# RobotFish.net
KiCad netlist of a schematic drawn in EAGLE
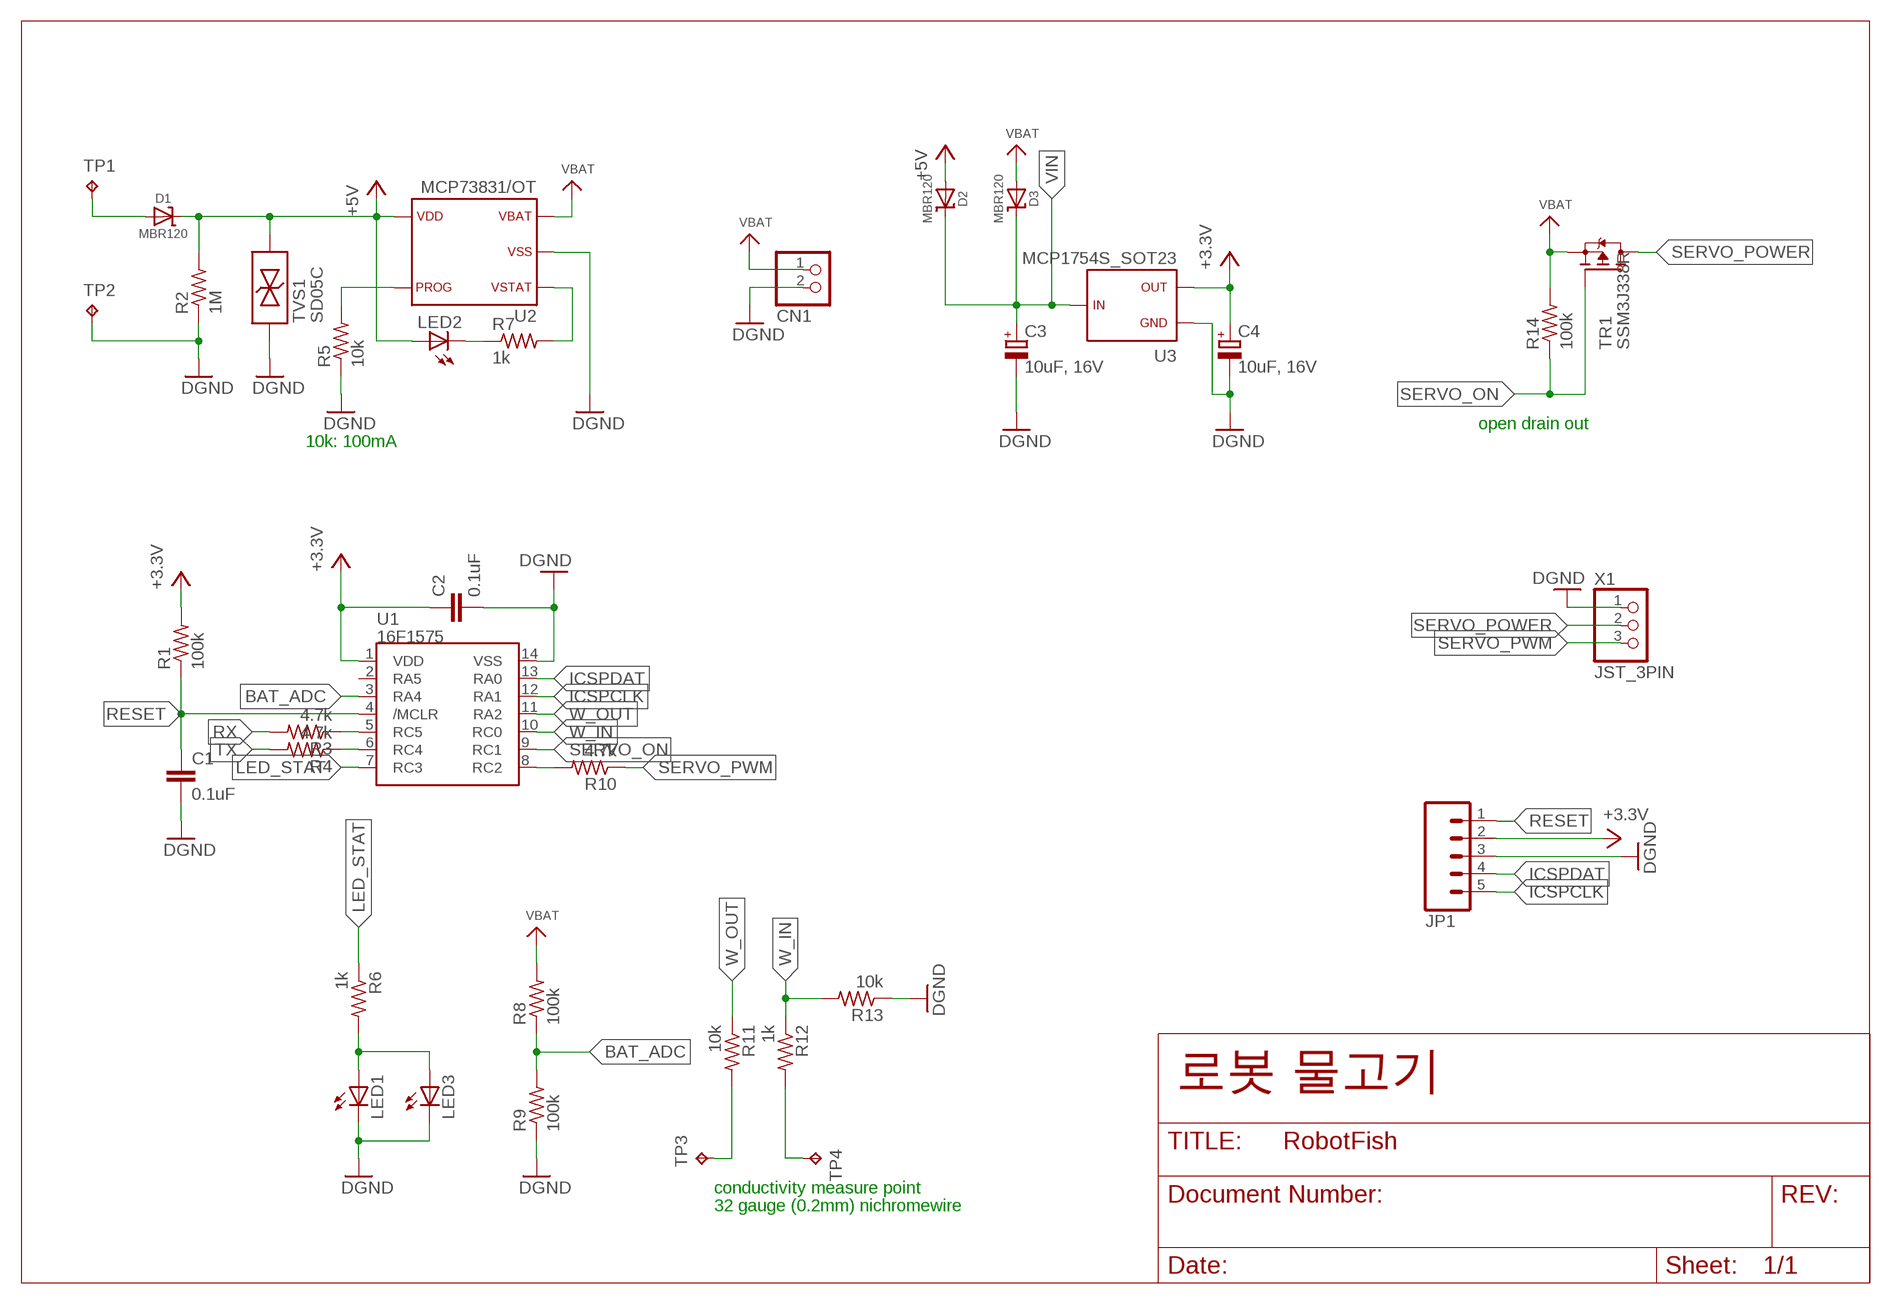
[diagram p0: schematic, sheet 1]

(export (version "E")
  (design (tool "Eeschema 10.0.6"))
  (components
    (comp (ref "C1")
      (value "0.1uF")
      (footprint "eagle-import:C0603(1608)")
      (libsource (lib "eagle-import") (part "C0603(1608)"))
    )
    (comp (ref "C2")
      (value "0.1uF")
      (footprint "eagle-import:C0603(1608)")
      (libsource (lib "eagle-import") (part "C0603(1608)"))
    )
    (comp (ref "C3")
      (value "10uF, 16V")
      (footprint "eagle-import:C1206(3216)-A")
      (libsource (lib "eagle-import") (part "C-TANTAL-A"))
    )
    (comp (ref "C4")
      (value "10uF, 16V")
      (footprint "eagle-import:C1206(3216)-A")
      (libsource (lib "eagle-import") (part "C-TANTAL-A"))
    )
    (comp (ref "CN1")
      (value "JST_2PIN-THM-RA")
      (footprint "eagle-import:JST-PH-2-THM-RA")
      (libsource (lib "eagle-import") (part "JST_2PIN-THM-RA"))
    )
    (comp (ref "D1")
      (value "MBR120")
      (footprint "eagle-import:SOD-123")
      (libsource (lib "eagle-import") (part "DIODE-SCHOTTKYSOD-123"))
    )
    (comp (ref "D2")
      (value "MBR120")
      (footprint "eagle-import:SOD-123")
      (libsource (lib "eagle-import") (part "DIODE-SCHOTTKYSOD-123"))
    )
    (comp (ref "D3")
      (value "MBR120")
      (footprint "eagle-import:SOD-123")
      (libsource (lib "eagle-import") (part "DIODE-SCHOTTKYSOD-123"))
    )
    (comp (ref "JP1")
      (value "M05PTH")
      (footprint "eagle-import:1X05")
      (libsource (lib "eagle-import") (part "M05PTH"))
    )
    (comp (ref "LED1")
      (value "LED0603")
      (footprint "eagle-import:LED-0603")
      (libsource (lib "eagle-import") (part "LED0603"))
    )
    (comp (ref "LED2")
      (value "LED0603")
      (footprint "eagle-import:LED-0603")
      (libsource (lib "eagle-import") (part "LED0603"))
    )
    (comp (ref "LED3")
      (value "LED3MM")
      (footprint "eagle-import:LED3MM")
      (libsource (lib "eagle-import") (part "LED3MM"))
    )
    (comp (ref "R1")
      (value "100k")
      (footprint "eagle-import:R0603(1608)")
      (libsource (lib "eagle-import") (part "R0603(1608)"))
    )
    (comp (ref "R2")
      (value "1M")
      (footprint "eagle-import:R0603(1608)")
      (libsource (lib "eagle-import") (part "R0603(1608)"))
    )
    (comp (ref "R3")
      (value "4.7k")
      (footprint "eagle-import:R0603(1608)")
      (libsource (lib "eagle-import") (part "R0603(1608)"))
    )
    (comp (ref "R4")
      (value "4.7k")
      (footprint "eagle-import:R0603(1608)")
      (libsource (lib "eagle-import") (part "R0603(1608)"))
    )
    (comp (ref "R5")
      (value "10k")
      (footprint "eagle-import:R0603(1608)")
      (libsource (lib "eagle-import") (part "R0603(1608)"))
    )
    (comp (ref "R6")
      (value "1k")
      (footprint "eagle-import:R0603(1608)")
      (libsource (lib "eagle-import") (part "R0603(1608)"))
    )
    (comp (ref "R7")
      (value "1k")
      (footprint "eagle-import:R0603(1608)")
      (libsource (lib "eagle-import") (part "R0603(1608)"))
    )
    (comp (ref "R8")
      (value "100k")
      (footprint "eagle-import:R0603(1608)")
      (libsource (lib "eagle-import") (part "R0603(1608)"))
    )
    (comp (ref "R9")
      (value "100k")
      (footprint "eagle-import:R0603(1608)")
      (libsource (lib "eagle-import") (part "R0603(1608)"))
    )
    (comp (ref "R10")
      (value "4.7k")
      (footprint "eagle-import:R0603(1608)")
      (libsource (lib "eagle-import") (part "R0603(1608)"))
    )
    (comp (ref "R11")
      (value "10k")
      (footprint "eagle-import:R0603(1608)")
      (libsource (lib "eagle-import") (part "R0603(1608)"))
    )
    (comp (ref "R12")
      (value "1k")
      (footprint "eagle-import:R0603(1608)")
      (libsource (lib "eagle-import") (part "R0603(1608)"))
    )
    (comp (ref "R13")
      (value "10k")
      (footprint "eagle-import:R0603(1608)")
      (libsource (lib "eagle-import") (part "R0603(1608)"))
    )
    (comp (ref "R14")
      (value "100k")
      (footprint "eagle-import:R0603(1608)")
      (libsource (lib "eagle-import") (part "R0603(1608)"))
    )
    (comp (ref "TP1")
      (value "TP-5010")
      (footprint "eagle-import:TP-5010")
      (libsource (lib "eagle-import") (part "TP-5010"))
    )
    (comp (ref "TP2")
      (value "TP-5010")
      (footprint "eagle-import:TP-5010")
      (libsource (lib "eagle-import") (part "TP-5010"))
    )
    (comp (ref "TP3")
      (value "TP-5010")
      (footprint "eagle-import:TP-5010")
      (libsource (lib "eagle-import") (part "TP-5010"))
    )
    (comp (ref "TP4")
      (value "TP-5010")
      (footprint "eagle-import:TP-5010")
      (libsource (lib "eagle-import") (part "TP-5010"))
    )
    (comp (ref "TR1")
      (value "SSM3J338R")
      (footprint "eagle-import:SOT23")
      (libsource (lib "eagle-import") (part "SSM3J338R"))
    )
    (comp (ref "TVS1")
      (value "SD05C")
      (footprint "eagle-import:SOD-323-NOPOL")
      (libsource (lib "eagle-import") (part "SD0"))
    )
    (comp (ref "U1")
      (value "16F1575")
      (footprint "eagle-import:SO-14")
      (libsource (lib "eagle-import") (part "16F1575"))
    )
    (comp (ref "U2")
      (value "MCP73831/OT")
      (footprint "eagle-import:SOT23-5L")
      (libsource (lib "eagle-import") (part "MCP73831/OT"))
    )
    (comp (ref "U3")
      (value "MCP1754S_SOT23")
      (footprint "eagle-import:SOT23")
      (libsource (lib "eagle-import") (part "MCP1754S_SOT23"))
    )
    (comp (ref "X1")
      (value "JST_3PIN")
      (footprint "eagle-import:SM03B-SRSS-TB")
      (libsource (lib "eagle-import") (part "JST_3PIN"))
    )
  )
  (nets
    (net (code "1") (name "+3.3V") (class "Default")
      (node (ref "C2") (pin "1") (pinfunction "1_1") (pintype "passive"))
      (node (ref "C4") (pin "1") (pinfunction "+_1") (pintype "passive"))
      (node (ref "JP1") (pin "2") (pinfunction "2_2") (pintype "passive"))
      (node (ref "R1") (pin "2") (pinfunction "2_2") (pintype "passive"))
      (node (ref "U1") (pin "1") (pinfunction "VDD_1") (pintype "bidirectional"))
      (node (ref "U3") (pin "2") (pinfunction "2_2") (pintype "power_in"))
    )
    (net (code "2") (name "+5V") (class "Default")
      (node (ref "D1") (pin "C") (pinfunction "C_C") (pintype "passive"))
      (node (ref "D2") (pin "A") (pinfunction "A_A") (pintype "passive"))
      (node (ref "LED2") (pin "A") (pinfunction "A_A") (pintype "passive"))
      (node (ref "R2") (pin "2") (pinfunction "2_2") (pintype "passive"))
      (node (ref "TVS1") (pin "2") (pinfunction "P$2_2") (pintype "bidirectional"))
      (node (ref "U2") (pin "4") (pinfunction "VDD_4") (pintype "power_in"))
    )
    (net (code "3") (name "BAT_ADC") (class "Default")
      (node (ref "R8") (pin "1") (pinfunction "1_1") (pintype "passive"))
      (node (ref "R9") (pin "2") (pinfunction "2_2") (pintype "passive"))
      (node (ref "U1") (pin "3") (pinfunction "RA4_3") (pintype "bidirectional"))
    )
    (net (code "4") (name "DGND") (class "Default")
      (node (ref "C1") (pin "2") (pinfunction "2_2") (pintype "passive"))
      (node (ref "C2") (pin "2") (pinfunction "2_2") (pintype "passive"))
      (node (ref "C3") (pin "2") (pinfunction "-_2") (pintype "passive"))
      (node (ref "C4") (pin "2") (pinfunction "-_2") (pintype "passive"))
      (node (ref "CN1") (pin "2") (pinfunction "1_2") (pintype "passive"))
      (node (ref "JP1") (pin "3") (pinfunction "3_3") (pintype "passive"))
      (node (ref "LED1") (pin "C") (pinfunction "C_C") (pintype "passive"))
      (node (ref "LED3") (pin "K") (pinfunction "C_K") (pintype "passive"))
      (node (ref "R13") (pin "1") (pinfunction "1_1") (pintype "passive"))
      (node (ref "R2") (pin "1") (pinfunction "1_1") (pintype "passive"))
      (node (ref "R5") (pin "1") (pinfunction "1_1") (pintype "passive"))
      (node (ref "R9") (pin "1") (pinfunction "1_1") (pintype "passive"))
      (node (ref "TP2") (pin "TP") (pinfunction "TP_TP") (pintype "input"))
      (node (ref "TVS1") (pin "1") (pinfunction "P$1_1") (pintype "bidirectional"))
      (node (ref "U1") (pin "14") (pinfunction "VSS_14") (pintype "bidirectional"))
      (node (ref "U2") (pin "2") (pinfunction "VSS_2") (pintype "power_in"))
      (node (ref "U3") (pin "1") (pinfunction "1_1") (pintype "power_in"))
      (node (ref "X1") (pin "1") (pinfunction "1_1") (pintype "passive"))
    )
    (net (code "5") (name "ICSPCLK") (class "Default")
      (node (ref "JP1") (pin "5") (pinfunction "5_5") (pintype "passive"))
      (node (ref "U1") (pin "12") (pinfunction "RA1_12") (pintype "bidirectional"))
    )
    (net (code "6") (name "ICSPDAT") (class "Default")
      (node (ref "JP1") (pin "4") (pinfunction "4_4") (pintype "passive"))
      (node (ref "U1") (pin "13") (pinfunction "RA0_13") (pintype "bidirectional"))
    )
    (net (code "7") (name "LED_STAT") (class "Default")
      (node (ref "R6") (pin "1") (pinfunction "1_1") (pintype "passive"))
      (node (ref "U1") (pin "7") (pinfunction "RC3_7") (pintype "bidirectional"))
    )
    (net (code "8") (name "Net-(D1-PadA)") (class "Default")
      (node (ref "D1") (pin "A") (pinfunction "A_A") (pintype "passive"))
      (node (ref "TP1") (pin "TP") (pinfunction "TP_TP") (pintype "input"))
    )
    (net (code "9") (name "Net-(LED1-PadA)") (class "Default")
      (node (ref "LED1") (pin "A") (pinfunction "A_A") (pintype "passive"))
      (node (ref "LED3") (pin "A") (pinfunction "A_A") (pintype "passive"))
      (node (ref "R6") (pin "2") (pinfunction "2_2") (pintype "passive"))
    )
    (net (code "10") (name "Net-(LED2-PadC)") (class "Default")
      (node (ref "LED2") (pin "C") (pinfunction "C_C") (pintype "passive"))
      (node (ref "R7") (pin "1") (pinfunction "1_1") (pintype "passive"))
    )
    (net (code "11") (name "Net-(R11-Pad2)") (class "Default")
      (node (ref "R11") (pin "2") (pinfunction "2_2") (pintype "passive"))
      (node (ref "TP3") (pin "TP") (pinfunction "TP_TP") (pintype "input"))
    )
    (net (code "12") (name "Net-(R12-Pad2)") (class "Default")
      (node (ref "R12") (pin "2") (pinfunction "2_2") (pintype "passive"))
      (node (ref "TP4") (pin "TP") (pinfunction "TP_TP") (pintype "input"))
    )
    (net (code "13") (name "Net-(U1-RC2)") (class "Default")
      (node (ref "R10") (pin "2") (pinfunction "2_2") (pintype "passive"))
      (node (ref "U1") (pin "8") (pinfunction "RC2_8") (pintype "bidirectional"))
    )
    (net (code "14") (name "Net-(U1-RC4)") (class "Default")
      (node (ref "R4") (pin "1") (pinfunction "1_1") (pintype "passive"))
      (node (ref "U1") (pin "6") (pinfunction "RC4_6") (pintype "bidirectional"))
    )
    (net (code "15") (name "Net-(U1-RC5)") (class "Default")
      (node (ref "R3") (pin "1") (pinfunction "1_1") (pintype "passive"))
      (node (ref "U1") (pin "5") (pinfunction "RC5_5") (pintype "bidirectional"))
    )
    (net (code "16") (name "Net-(U2-PROG)") (class "Default")
      (node (ref "R5") (pin "2") (pinfunction "2_2") (pintype "passive"))
      (node (ref "U2") (pin "5") (pinfunction "PROG_5") (pintype "input"))
    )
    (net (code "17") (name "Net-(U2-STAT)") (class "Default")
      (node (ref "R7") (pin "2") (pinfunction "2_2") (pintype "passive"))
      (node (ref "U2") (pin "1") (pinfunction "STAT_1") (pintype "output"))
    )
    (net (code "18") (name "RESET") (class "Default")
      (node (ref "C1") (pin "1") (pinfunction "1_1") (pintype "passive"))
      (node (ref "JP1") (pin "1") (pinfunction "1_1") (pintype "passive"))
      (node (ref "R1") (pin "1") (pinfunction "1_1") (pintype "passive"))
      (node (ref "U1") (pin "4") (pinfunction "/MCLR_4") (pintype "bidirectional"))
    )
    (net (code "19") (name "RX") (class "Default")
      (node (ref "R3") (pin "2") (pinfunction "2_2") (pintype "passive"))
    )
    (net (code "20") (name "SERVO_ON") (class "Default")
      (node (ref "R14") (pin "1") (pinfunction "1_1") (pintype "passive"))
      (node (ref "TR1") (pin "1") (pinfunction "G_1") (pintype "passive"))
      (node (ref "U1") (pin "9") (pinfunction "RC1_9") (pintype "bidirectional"))
    )
    (net (code "21") (name "SERVO_POWER") (class "Default")
      (node (ref "TR1") (pin "3") (pinfunction "D_3") (pintype "passive"))
      (node (ref "X1") (pin "2") (pinfunction "2_2") (pintype "passive"))
    )
    (net (code "22") (name "SERVO_PWM") (class "Default")
      (node (ref "R10") (pin "1") (pinfunction "1_1") (pintype "passive"))
      (node (ref "X1") (pin "3") (pinfunction "3_3") (pintype "passive"))
    )
    (net (code "23") (name "TX") (class "Default")
      (node (ref "R4") (pin "2") (pinfunction "2_2") (pintype "passive"))
    )
    (net (code "24") (name "VBAT") (class "Default")
      (node (ref "CN1") (pin "1") (pinfunction "2_1") (pintype "passive"))
      (node (ref "D3") (pin "A") (pinfunction "A_A") (pintype "passive"))
      (node (ref "R14") (pin "2") (pinfunction "2_2") (pintype "passive"))
      (node (ref "R8") (pin "2") (pinfunction "2_2") (pintype "passive"))
      (node (ref "TR1") (pin "2") (pinfunction "S_2") (pintype "passive"))
      (node (ref "U2") (pin "3") (pinfunction "VBAT_3") (pintype "bidirectional"))
    )
    (net (code "25") (name "VIN") (class "Default")
      (node (ref "C3") (pin "1") (pinfunction "+_1") (pintype "passive"))
      (node (ref "D2") (pin "C") (pinfunction "C_C") (pintype "passive"))
      (node (ref "D3") (pin "C") (pinfunction "C_C") (pintype "passive"))
      (node (ref "U3") (pin "3") (pinfunction "3_3") (pintype "power_in"))
    )
    (net (code "26") (name "W_IN") (class "Default")
      (node (ref "R12") (pin "1") (pinfunction "1_1") (pintype "passive"))
      (node (ref "R13") (pin "2") (pinfunction "2_2") (pintype "passive"))
      (node (ref "U1") (pin "10") (pinfunction "RC0_10") (pintype "bidirectional"))
    )
    (net (code "27") (name "W_OUT") (class "Default")
      (node (ref "R11") (pin "1") (pinfunction "1_1") (pintype "passive"))
      (node (ref "U1") (pin "11") (pinfunction "RA2_11") (pintype "bidirectional"))
    )
    (net (code "28") (name "unconnected-(U1-RA5-Pad2)") (class "Default")
      (node (ref "U1") (pin "2") (pinfunction "RA5_2") (pintype "bidirectional"))
    )
  )
)
